# 780-00055_rev2_Pg4_SCH_NRES_Temp_Meas_8-.net
KiCad netlist of a schematic drawn in Altium Designer
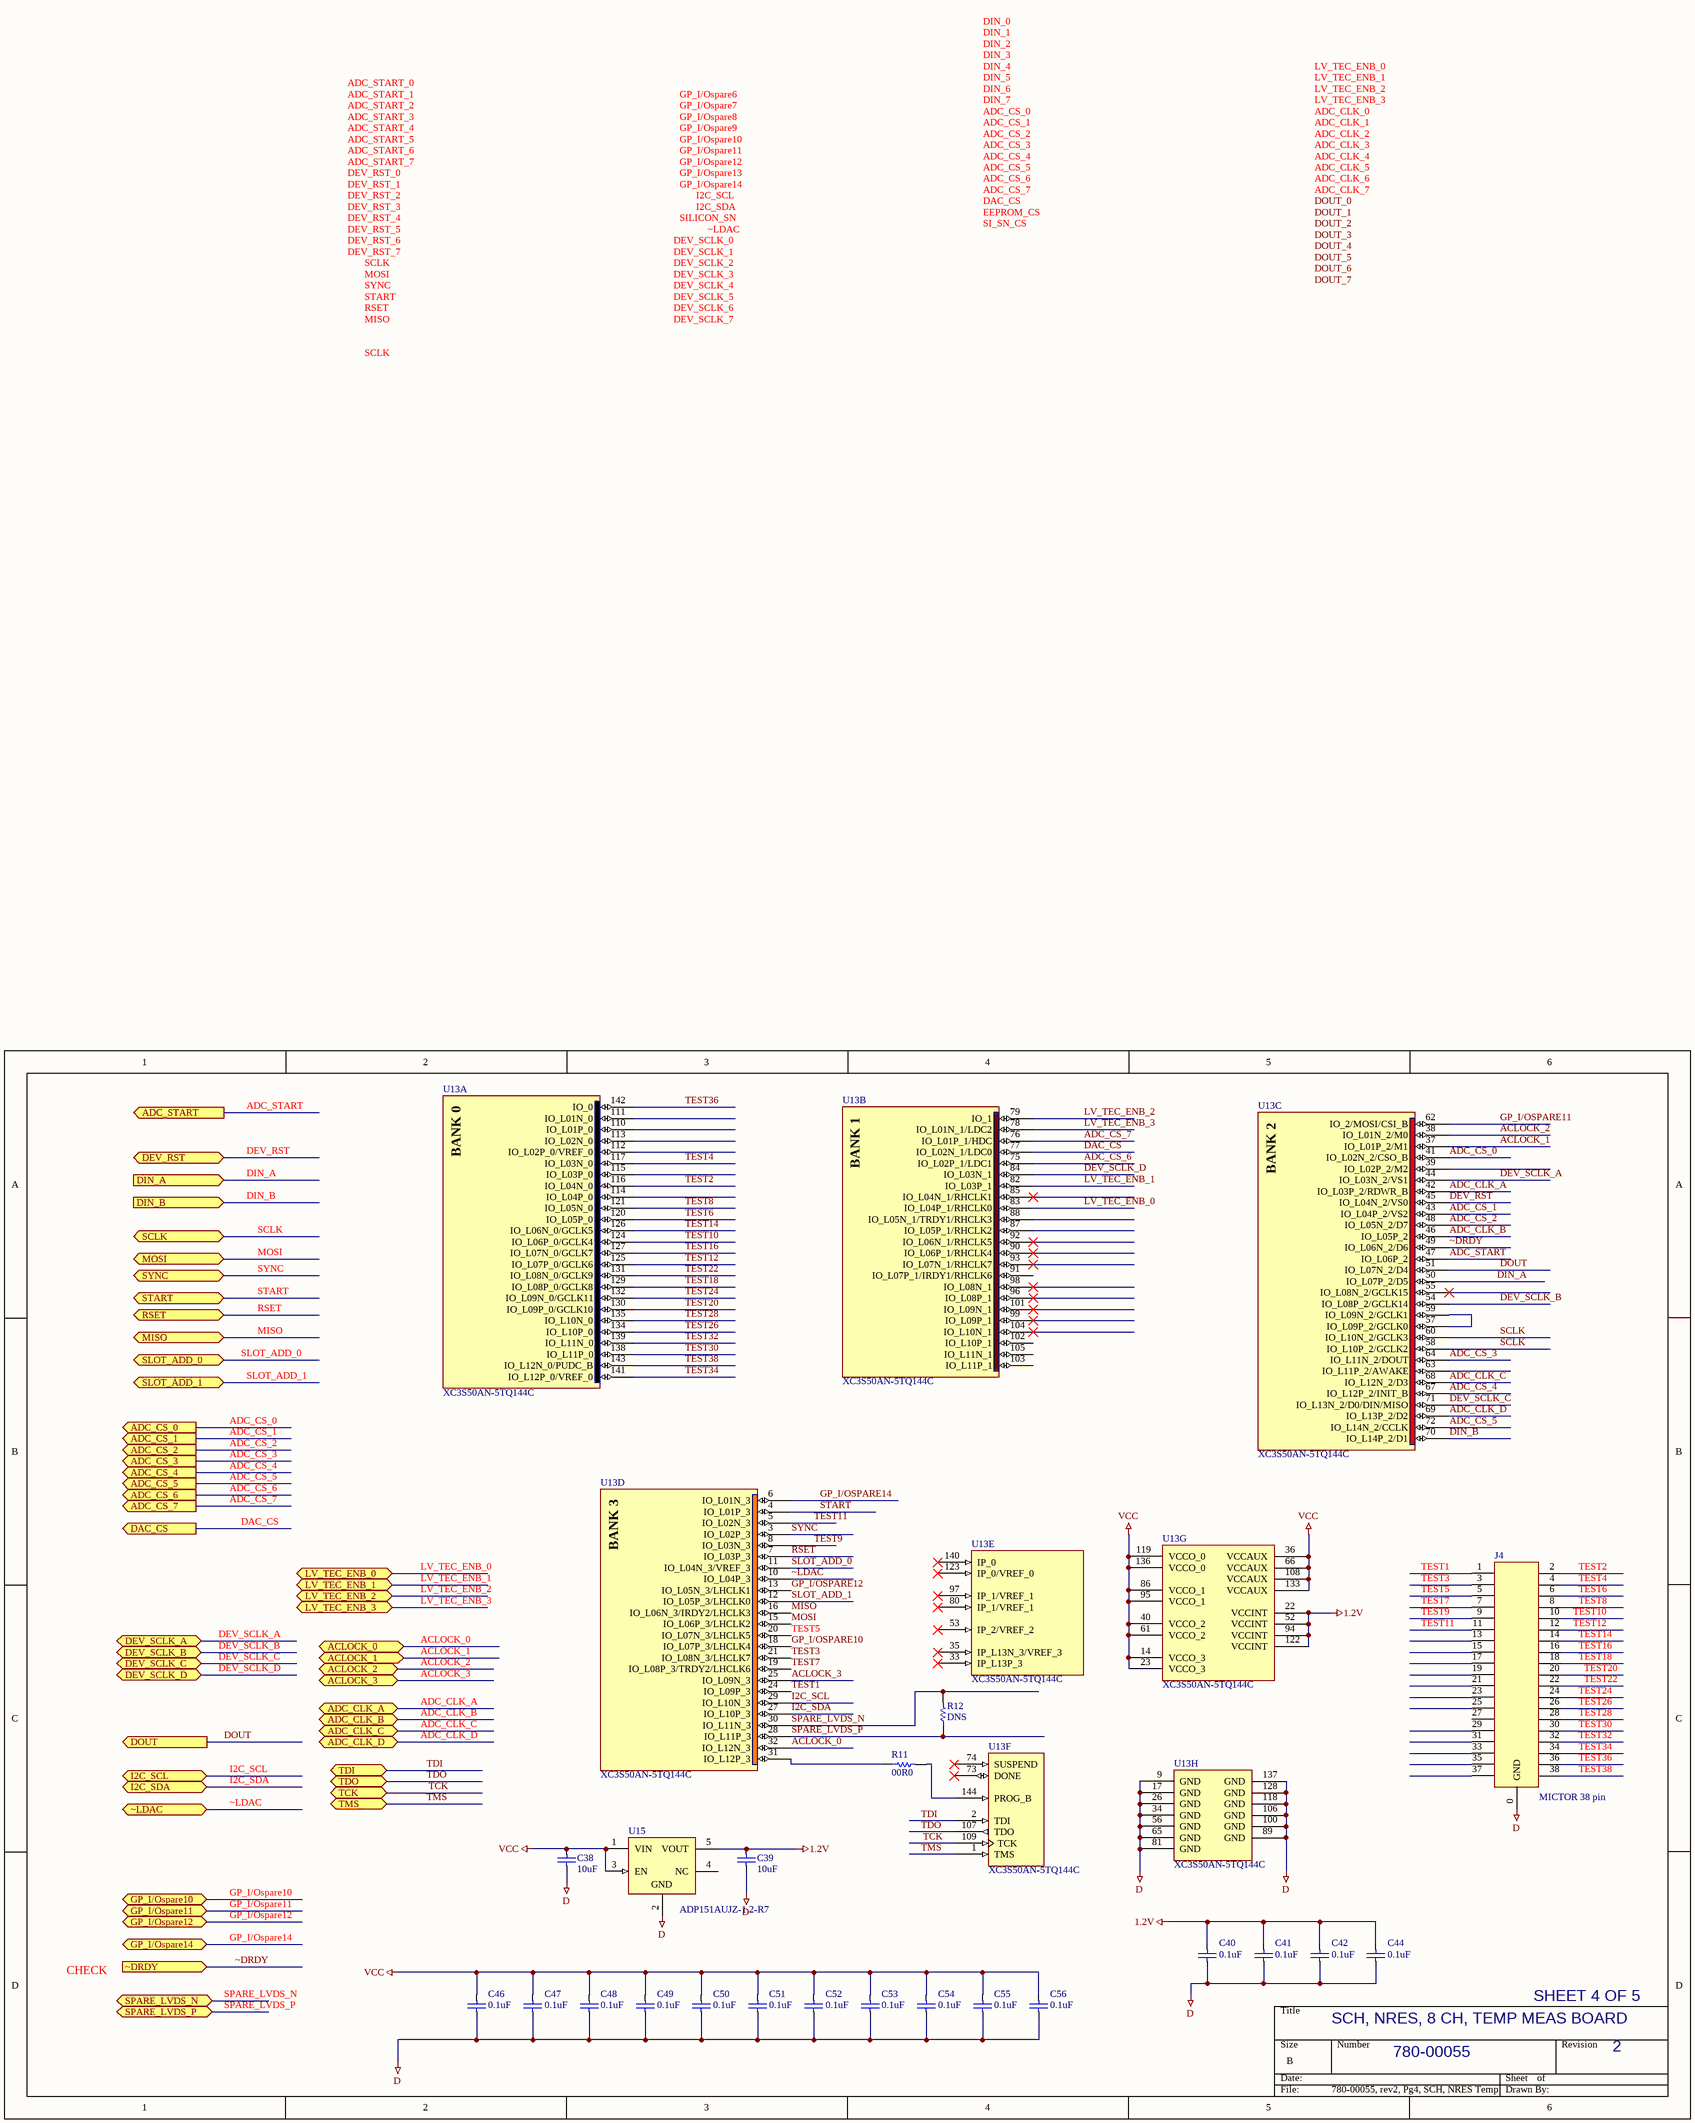
[diagram p0: 780-00055, rev2, Pg4, SCH, NRES Temp Meas, 8-Chan RTD .SchDoc]

(export (version "E")
  (design (tool "Eeschema 10.0.6"))
  (components
    (comp (ref "C38")
      (value "10uF")
      (footprint "Protel 99SE BANKS PCB:smd_0805")
      (description "Capacitor")
      (fields (field (name "Comment") "Cap SMD"))
      (libsource (lib "Richs Schematic Components") (part "Cap SMD"))
    )
    (comp (ref "C39")
      (value "10uF")
      (footprint "Protel 99SE BANKS PCB:smd_0805")
      (description "Capacitor")
      (fields (field (name "Comment") "Cap SMD"))
      (libsource (lib "Richs Schematic Components") (part "Cap SMD"))
    )
    (comp (ref "C40")
      (value "0.1uF")
      (footprint "SMD_0805")
      (description "Capacitor")
      (fields (field (name "Comment") "Cap SMD"))
      (libsource (lib "Richs Schematic Components") (part "Cap SMD"))
    )
    (comp (ref "C41")
      (value "0.1uF")
      (footprint "SMD_0805")
      (description "Capacitor")
      (fields (field (name "Comment") "Cap SMD"))
      (libsource (lib "Richs Schematic Components") (part "Cap SMD"))
    )
    (comp (ref "C42")
      (value "0.1uF")
      (footprint "SMD_0805")
      (description "Capacitor")
      (fields (field (name "Comment") "Cap SMD"))
      (libsource (lib "Richs Schematic Components") (part "Cap SMD"))
    )
    (comp (ref "C44")
      (value "0.1uF")
      (footprint "SMD_0805")
      (description "Capacitor")
      (fields (field (name "Comment") "Cap SMD"))
      (libsource (lib "Richs Schematic Components") (part "Cap SMD"))
    )
    (comp (ref "C46")
      (value "0.1uF")
      (footprint "SMD_0805")
      (description "Capacitor")
      (fields (field (name "Comment") "Cap SMD"))
      (libsource (lib "Richs Schematic Components") (part "Cap SMD"))
    )
    (comp (ref "C47")
      (value "0.1uF")
      (footprint "SMD_0805")
      (description "Capacitor")
      (fields (field (name "Comment") "Cap SMD"))
      (libsource (lib "Richs Schematic Components") (part "Cap SMD"))
    )
    (comp (ref "C48")
      (value "0.1uF")
      (footprint "SMD_0805")
      (description "Capacitor")
      (fields (field (name "Comment") "Cap SMD"))
      (libsource (lib "Richs Schematic Components") (part "Cap SMD"))
    )
    (comp (ref "C49")
      (value "0.1uF")
      (footprint "SMD_0805")
      (description "Capacitor")
      (fields (field (name "Comment") "Cap SMD"))
      (libsource (lib "Richs Schematic Components") (part "Cap SMD"))
    )
    (comp (ref "C50")
      (value "0.1uF")
      (footprint "SMD_0805")
      (description "Capacitor")
      (fields (field (name "Comment") "Cap SMD"))
      (libsource (lib "Richs Schematic Components") (part "Cap SMD"))
    )
    (comp (ref "C51")
      (value "0.1uF")
      (footprint "SMD_0805")
      (description "Capacitor")
      (fields (field (name "Comment") "Cap SMD"))
      (libsource (lib "Richs Schematic Components") (part "Cap SMD"))
    )
    (comp (ref "C52")
      (value "0.1uF")
      (footprint "SMD_0805")
      (description "Capacitor")
      (fields (field (name "Comment") "Cap SMD"))
      (libsource (lib "Richs Schematic Components") (part "Cap SMD"))
    )
    (comp (ref "C53")
      (value "0.1uF")
      (footprint "SMD_0805")
      (description "Capacitor")
      (fields (field (name "Comment") "Cap SMD"))
      (libsource (lib "Richs Schematic Components") (part "Cap SMD"))
    )
    (comp (ref "C54")
      (value "0.1uF")
      (footprint "SMD_0805")
      (description "Capacitor")
      (fields (field (name "Comment") "Cap SMD"))
      (libsource (lib "Richs Schematic Components") (part "Cap SMD"))
    )
    (comp (ref "C55")
      (value "0.1uF")
      (footprint "SMD_0805")
      (description "Capacitor")
      (fields (field (name "Comment") "Cap SMD"))
      (libsource (lib "Richs Schematic Components") (part "Cap SMD"))
    )
    (comp (ref "C56")
      (value "0.1uF")
      (footprint "SMD_0805")
      (description "Capacitor")
      (fields (field (name "Comment") "Cap SMD"))
      (libsource (lib "Richs Schematic Components") (part "Cap SMD"))
    )
    (comp (ref "J4")
      (value "MICTOR 38 pin")
      (footprint "MICTOR 38 pin connector")
      (description "38 pin MICTOR Adapter")
      (fields (field (name "MANUFACTURER") "TE Connectivity"))
      (libsource (lib "Richs Schematic Components") (part "MICTOR Adapter"))
    )
    (comp (ref "R11")
      (value "00R0")
      (footprint "SMD_0805")
      (description "Resistor 0805")
      (fields (field (name "MANUFACTURER") "Vishay/Dale") (field (name "Comment") "Res 0805"))
      (libsource (lib "Richs Schematic Components") (part "Res SMD"))
    )
    (comp (ref "R12")
      (value "DNS")
      (footprint "SMD_0805")
      (description "Resistor 0805")
      (fields (field (name "MANUFACTURER") "Vishay/Dale") (field (name "Comment") "Res 0805"))
      (libsource (lib "Richs Schematic Components") (part "Res SMD"))
    )
    (comp (ref "U13")
      (value "XC3S50AN-5TQ144C")
      (footprint "TQ144_N")
      (description "Spartan-3AN Non-Volatile FPGA, 108 User I/Os, 144-Pin TQFP, High Performance, Commercial Grade")
      (fields (field (name "PUBLISHER") "Altium Limited"))
      (libsource (lib "Xilinx Spartan-3AN") (part "XC3S50AN-5TQ144C"))
    )
    (comp (ref "U15")
      (value "ADP151AUJZ-1.2-R7")
      (footprint "ADI-UJ-5_N")
      (fields (field (name "MANUFACTURER") "Analog Devices"))
      (libsource (lib "Altium Content Vault") (part "ADI-ADP1XX-UJ-5"))
    )
  )
  (nets
    (net (code "1") (name "/ACLOCK_0") (class "Default")
      (node (ref "U13") (pin "32") (pinfunction "IO_L12N_3_32") (pintype "bidirectional"))
    )
    (net (code "2") (name "/ACLOCK_1") (class "Default")
      (node (ref "U13") (pin "37") (pinfunction "IO_L01P_2/M1_37") (pintype "bidirectional"))
    )
    (net (code "3") (name "/ACLOCK_2") (class "Default")
      (node (ref "U13") (pin "38") (pinfunction "IO_L01N_2/M0_38") (pintype "bidirectional"))
    )
    (net (code "4") (name "/ACLOCK_3") (class "Default")
      (node (ref "U13") (pin "25") (pinfunction "IO_L09N_3_25") (pintype "bidirectional"))
    )
    (net (code "13") (name "/ADC_CLK_A") (class "Default")
      (node (ref "U13") (pin "42") (pinfunction "IO_L03P_2/RDWR_B_42") (pintype "bidirectional"))
    )
    (net (code "14") (name "/ADC_CLK_B") (class "Default")
      (node (ref "U13") (pin "46") (pinfunction "IO_L05P_2_46") (pintype "bidirectional"))
    )
    (net (code "15") (name "/ADC_CLK_C") (class "Default")
      (node (ref "U13") (pin "68") (pinfunction "IO_L12N_2/D3_68") (pintype "bidirectional"))
    )
    (net (code "16") (name "/ADC_CLK_D") (class "Default")
      (node (ref "U13") (pin "69") (pinfunction "IO_L13P_2/D2_69") (pintype "bidirectional"))
    )
    (net (code "17") (name "/ADC_CS_0") (class "Default")
      (node (ref "U13") (pin "41") (pinfunction "IO_L02N_2/CSO_B_41") (pintype "bidirectional"))
    )
    (net (code "18") (name "/ADC_CS_1") (class "Default")
      (node (ref "U13") (pin "43") (pinfunction "IO_L04P_2/VS2_43") (pintype "bidirectional"))
    )
    (net (code "19") (name "/ADC_CS_2") (class "Default")
      (node (ref "U13") (pin "48") (pinfunction "IO_L05N_2/D7_48") (pintype "bidirectional"))
    )
    (net (code "20") (name "/ADC_CS_3") (class "Default")
      (node (ref "U13") (pin "64") (pinfunction "IO_L11N_2/DOUT_64") (pintype "bidirectional"))
    )
    (net (code "21") (name "/ADC_CS_4") (class "Default")
      (node (ref "U13") (pin "67") (pinfunction "IO_L12P_2/INIT_B_67") (pintype "bidirectional"))
    )
    (net (code "22") (name "/ADC_CS_5") (class "Default")
      (node (ref "U13") (pin "72") (pinfunction "IO_L14N_2/CCLK_72") (pintype "bidirectional"))
    )
    (net (code "23") (name "/ADC_CS_6") (class "Default")
      (node (ref "U13") (pin "75") (pinfunction "IO_L02P_1/LDC1_75") (pintype "bidirectional"))
    )
    (net (code "24") (name "/ADC_CS_7") (class "Default")
      (node (ref "U13") (pin "76") (pinfunction "IO_L01P_1/HDC_76") (pintype "bidirectional"))
    )
    (net (code "25") (name "/ADC_START") (class "Default")
      (node (ref "U13") (pin "47") (pinfunction "IO_L06P_2_47") (pintype "bidirectional"))
    )
    (net (code "34") (name "/DAC_CS") (class "Default")
      (node (ref "U13") (pin "77") (pinfunction "IO_L02N_1/LDC0_77") (pintype "bidirectional"))
    )
    (net (code "35") (name "/DEV_RST") (class "Default")
      (node (ref "U13") (pin "45") (pinfunction "IO_L04N_2/VS0_45") (pintype "bidirectional"))
    )
    (net (code "52") (name "/DEV_SCLK_A") (class "Default")
      (node (ref "U13") (pin "44") (pinfunction "IO_L03N_2/VS1_44") (pintype "bidirectional"))
    )
    (net (code "53") (name "/DEV_SCLK_B") (class "Default")
      (node (ref "U13") (pin "54") (pinfunction "IO_L08P_2/GCLK14_54") (pintype "bidirectional"))
    )
    (net (code "54") (name "/DEV_SCLK_C") (class "Default")
      (node (ref "U13") (pin "71") (pinfunction "IO_L13N_2/D0/DIN/MISO_71") (pintype "bidirectional"))
    )
    (net (code "55") (name "/DEV_SCLK_D") (class "Default")
      (node (ref "U13") (pin "84") (pinfunction "IO_L03N_1_84") (pintype "bidirectional"))
    )
    (net (code "64") (name "/DIN_A") (class "Default")
      (node (ref "U13") (pin "50") (pinfunction "IO_L07P_2/D5_50") (pintype "bidirectional"))
    )
    (net (code "65") (name "/DIN_B") (class "Default")
      (node (ref "U13") (pin "70") (pinfunction "IO_L14P_2/D1_70") (pintype "bidirectional"))
    )
    (net (code "66") (name "/DOUT") (class "Default")
      (node (ref "U13") (pin "51") (pinfunction "IO_L07N_2/D4_51") (pintype "bidirectional"))
    )
    (net (code "76") (name "/GP_I{slash}OSPARE10") (class "Default")
      (node (ref "U13") (pin "18") (pinfunction "IO_L07P_3/LHCLK4_18") (pintype "bidirectional"))
    )
    (net (code "77") (name "/GP_I{slash}OSPARE11") (class "Default")
      (node (ref "U13") (pin "62") (pinfunction "IO_2/MOSI/CSI_B_62") (pintype "bidirectional"))
    )
    (net (code "78") (name "/GP_I{slash}OSPARE12") (class "Default")
      (node (ref "U13") (pin "13") (pinfunction "IO_L05N_3/LHCLK1_13") (pintype "bidirectional"))
    )
    (net (code "79") (name "/GP_I{slash}OSPARE14") (class "Default")
      (node (ref "U13") (pin "6") (pinfunction "IO_L01N_3_6") (pintype "bidirectional"))
    )
    (net (code "89") (name "/I2C_SCL") (class "Default")
      (node (ref "U13") (pin "29") (pinfunction "IO_L10N_3_29") (pintype "bidirectional"))
    )
    (net (code "90") (name "/I2C_SDA") (class "Default")
      (node (ref "U13") (pin "27") (pinfunction "IO_L10P_3_27") (pintype "bidirectional"))
    )
    (net (code "91") (name "/LV_TEC_ENB_0") (class "Default")
      (node (ref "U13") (pin "83") (pinfunction "IO_L04P_1/RHCLK0_83") (pintype "bidirectional"))
    )
    (net (code "92") (name "/LV_TEC_ENB_1") (class "Default")
      (node (ref "U13") (pin "82") (pinfunction "IO_L03P_1_82") (pintype "bidirectional"))
    )
    (net (code "93") (name "/LV_TEC_ENB_2") (class "Default")
      (node (ref "U13") (pin "79") (pinfunction "IO_1_79") (pintype "bidirectional"))
    )
    (net (code "94") (name "/LV_TEC_ENB_3") (class "Default")
      (node (ref "U13") (pin "78") (pinfunction "IO_L01N_1/LDC2_78") (pintype "bidirectional"))
    )
    (net (code "95") (name "/MISO") (class "Default")
      (node (ref "U13") (pin "16") (pinfunction "IO_L06N_3/IRDY2/LHCLK3_16") (pintype "bidirectional"))
    )
    (net (code "96") (name "/MOSI") (class "Default")
      (node (ref "U13") (pin "15") (pinfunction "IO_L06P_3/LHCLK2_15") (pintype "bidirectional"))
    )
    (net (code "97") (name "/RSET") (class "Default")
      (node (ref "U13") (pin "7") (pinfunction "IO_L03P_3_7") (pintype "bidirectional"))
    )
    (net (code "98") (name "/SCLK") (class "Default")
      (node (ref "U13") (pin "58") (pinfunction "IO_L10P_2/GCLK2_58") (pintype "bidirectional"))
      (node (ref "U13") (pin "60") (pinfunction "IO_L10N_2/GCLK3_60") (pintype "bidirectional"))
    )
    (net (code "101") (name "/SLOT_ADD_0") (class "Default")
      (node (ref "U13") (pin "11") (pinfunction "IO_L04N_3/VREF_3_11") (pintype "bidirectional"))
    )
    (net (code "102") (name "/SLOT_ADD_1") (class "Default")
      (node (ref "U13") (pin "12") (pinfunction "IO_L05P_3/LHCLK0_12") (pintype "bidirectional"))
    )
    (net (code "103") (name "/SPARE_LVDS_N") (class "Default")
      (node (ref "R12") (pin "2") (pinfunction "2_2") (pintype "passive"))
      (node (ref "U13") (pin "30") (pinfunction "IO_L11N_3_30") (pintype "bidirectional"))
    )
    (net (code "104") (name "/SPARE_LVDS_P") (class "Default")
      (node (ref "R12") (pin "1") (pinfunction "1_1") (pintype "passive"))
      (node (ref "U13") (pin "28") (pinfunction "IO_L11P_3_28") (pintype "bidirectional"))
    )
    (net (code "105") (name "/START") (class "Default")
      (node (ref "U13") (pin "4") (pinfunction "IO_L01P_3_4") (pintype "bidirectional"))
    )
    (net (code "106") (name "/SYNC") (class "Default")
      (node (ref "U13") (pin "3") (pinfunction "IO_L02P_3_3") (pintype "bidirectional"))
    )
    (net (code "107") (name "/TCK") (class "Default")
      (node (ref "U13") (pin "109") (pinfunction "TCK_109") (pintype "input"))
    )
    (net (code "108") (name "/TDI") (class "Default")
      (node (ref "U13") (pin "2") (pinfunction "TDI_2") (pintype "input"))
    )
    (net (code "109") (name "/TDO") (class "Default")
      (node (ref "U13") (pin "107") (pinfunction "TDO_107") (pintype "output"))
    )
    (net (code "110") (name "/TEST1") (class "Default")
      (node (ref "J4") (pin "1") (pinfunction "display_1") (pintype "passive"))
      (node (ref "U13") (pin "24") (pinfunction "IO_L09P_3_24") (pintype "bidirectional"))
    )
    (net (code "111") (name "/TEST2") (class "Default")
      (node (ref "J4") (pin "2") (pinfunction "conn_2") (pintype "passive"))
      (node (ref "U13") (pin "116") (pinfunction "IO_L04N_0_116") (pintype "bidirectional"))
    )
    (net (code "112") (name "/TEST3") (class "Default")
      (node (ref "J4") (pin "3") (pinfunction "conn_3") (pintype "passive"))
      (node (ref "U13") (pin "21") (pinfunction "IO_L08N_3/LHCLK7_21") (pintype "bidirectional"))
    )
    (net (code "113") (name "/TEST4") (class "Default")
      (node (ref "J4") (pin "4") (pinfunction "conn_4") (pintype "passive"))
      (node (ref "U13") (pin "117") (pinfunction "IO_L03N_0_117") (pintype "bidirectional"))
    )
    (net (code "114") (name "/TEST5") (class "Default")
      (node (ref "J4") (pin "5") (pinfunction "conn_5") (pintype "passive"))
      (node (ref "U13") (pin "20") (pinfunction "IO_L07N_3/LHCLK5_20") (pintype "bidirectional"))
    )
    (net (code "115") (name "/TEST6") (class "Default")
      (node (ref "J4") (pin "6") (pinfunction "conn_6") (pintype "passive"))
      (node (ref "U13") (pin "120") (pinfunction "IO_L05P_0_120") (pintype "bidirectional"))
    )
    (net (code "116") (name "/TEST7") (class "Default")
      (node (ref "J4") (pin "7") (pinfunction "conn_7") (pintype "passive"))
      (node (ref "U13") (pin "19") (pinfunction "IO_L08P_3/TRDY2/LHCLK6_19") (pintype "bidirectional"))
    )
    (net (code "117") (name "/TEST8") (class "Default")
      (node (ref "J4") (pin "8") (pinfunction "conn_8") (pintype "passive"))
      (node (ref "U13") (pin "121") (pinfunction "IO_L05N_0_121") (pintype "bidirectional"))
    )
    (net (code "118") (name "/TEST9") (class "Default")
      (node (ref "J4") (pin "9") (pinfunction "conn_9") (pintype "passive"))
      (node (ref "U13") (pin "8") (pinfunction "IO_L03N_3_8") (pintype "bidirectional"))
    )
    (net (code "119") (name "/TEST10") (class "Default")
      (node (ref "J4") (pin "10") (pinfunction "conn_10") (pintype "passive"))
      (node (ref "U13") (pin "124") (pinfunction "IO_L06P_0/GCLK4_124") (pintype "bidirectional"))
    )
    (net (code "120") (name "/TEST11") (class "Default")
      (node (ref "J4") (pin "11") (pinfunction "conn_11") (pintype "passive"))
      (node (ref "U13") (pin "5") (pinfunction "IO_L02N_3_5") (pintype "bidirectional"))
    )
    (net (code "121") (name "/TEST12") (class "Default")
      (node (ref "J4") (pin "12") (pinfunction "conn_12") (pintype "passive"))
      (node (ref "U13") (pin "125") (pinfunction "IO_L07P_0/GCLK6_125") (pintype "bidirectional"))
    )
    (net (code "122") (name "/TEST14") (class "Default")
      (node (ref "J4") (pin "14") (pinfunction "conn_14") (pintype "passive"))
      (node (ref "U13") (pin "126") (pinfunction "IO_L06N_0/GCLK5_126") (pintype "bidirectional"))
    )
    (net (code "123") (name "/TEST16") (class "Default")
      (node (ref "J4") (pin "16") (pinfunction "conn_16") (pintype "passive"))
      (node (ref "U13") (pin "127") (pinfunction "IO_L07N_0/GCLK7_127") (pintype "bidirectional"))
    )
    (net (code "124") (name "/TEST18") (class "Default")
      (node (ref "J4") (pin "18") (pinfunction "conn_18") (pintype "passive"))
      (node (ref "U13") (pin "129") (pinfunction "IO_L08P_0/GCLK8_129") (pintype "bidirectional"))
    )
    (net (code "125") (name "/TEST20") (class "Default")
      (node (ref "J4") (pin "20") (pinfunction "conn_20") (pintype "passive"))
      (node (ref "U13") (pin "130") (pinfunction "IO_L09P_0/GCLK10_130") (pintype "bidirectional"))
    )
    (net (code "126") (name "/TEST22") (class "Default")
      (node (ref "J4") (pin "22") (pinfunction "conn_22") (pintype "passive"))
      (node (ref "U13") (pin "131") (pinfunction "IO_L08N_0/GCLK9_131") (pintype "bidirectional"))
    )
    (net (code "127") (name "/TEST24") (class "Default")
      (node (ref "J4") (pin "24") (pinfunction "conn_24") (pintype "passive"))
      (node (ref "U13") (pin "132") (pinfunction "IO_L09N_0/GCLK11_132") (pintype "bidirectional"))
    )
    (net (code "128") (name "/TEST26") (class "Default")
      (node (ref "J4") (pin "26") (pinfunction "conn_26") (pintype "passive"))
      (node (ref "U13") (pin "134") (pinfunction "IO_L10P_0_134") (pintype "bidirectional"))
    )
    (net (code "129") (name "/TEST28") (class "Default")
      (node (ref "J4") (pin "28") (pinfunction "conn_28") (pintype "passive"))
      (node (ref "U13") (pin "135") (pinfunction "IO_L10N_0_135") (pintype "bidirectional"))
    )
    (net (code "130") (name "/TEST30") (class "Default")
      (node (ref "J4") (pin "30") (pinfunction "conn_30") (pintype "passive"))
      (node (ref "U13") (pin "138") (pinfunction "IO_L11P_0_138") (pintype "bidirectional"))
    )
    (net (code "131") (name "/TEST32") (class "Default")
      (node (ref "J4") (pin "32") (pinfunction "conn_32") (pintype "passive"))
      (node (ref "U13") (pin "139") (pinfunction "IO_L11N_0_139") (pintype "bidirectional"))
    )
    (net (code "132") (name "/TEST34") (class "Default")
      (node (ref "J4") (pin "34") (pinfunction "conn_34") (pintype "passive"))
      (node (ref "U13") (pin "141") (pinfunction "IO_L12P_0/VREF_0_141") (pintype "bidirectional"))
    )
    (net (code "133") (name "/TEST36") (class "Default")
      (node (ref "J4") (pin "36") (pinfunction "conn_36") (pintype "passive"))
      (node (ref "U13") (pin "142") (pinfunction "IO_0_142") (pintype "bidirectional"))
    )
    (net (code "134") (name "/TEST38") (class "Default")
      (node (ref "J4") (pin "38") (pinfunction "conn_38") (pintype "passive"))
      (node (ref "U13") (pin "143") (pinfunction "IO_L12N_0/PUDC_B_143") (pintype "bidirectional"))
    )
    (net (code "135") (name "/TMS") (class "Default")
      (node (ref "U13") (pin "1") (pinfunction "TMS_1") (pintype "input"))
    )
    (net (code "136") (name "/~DRDY") (class "Default")
      (node (ref "U13") (pin "49") (pinfunction "IO_L06N_2/D6_49") (pintype "bidirectional"))
    )
    (net (code "137") (name "/~LDAC") (class "Default")
      (node (ref "U13") (pin "10") (pinfunction "IO_L04P_3_10") (pintype "bidirectional"))
    )
    (net (code "138") (name "1.2V") (class "Default")
      (node (ref "C39") (pin "2") (pinfunction "2_2") (pintype "passive"))
      (node (ref "C40") (pin "2") (pinfunction "2_2") (pintype "passive"))
      (node (ref "C41") (pin "2") (pinfunction "2_2") (pintype "passive"))
      (node (ref "C42") (pin "2") (pinfunction "2_2") (pintype "passive"))
      (node (ref "C44") (pin "2") (pinfunction "2_2") (pintype "passive"))
      (node (ref "U13") (pin "122") (pinfunction "VCCINT_122") (pintype "power_in"))
      (node (ref "U13") (pin "22") (pinfunction "VCCINT_22") (pintype "power_in"))
      (node (ref "U13") (pin "52") (pinfunction "VCCINT_52") (pintype "power_in"))
      (node (ref "U13") (pin "94") (pinfunction "VCCINT_94") (pintype "power_in"))
      (node (ref "U15") (pin "5") (pinfunction "VOUT_5") (pintype "power_in"))
    )
    (net (code "139") (name "D") (class "Default")
      (node (ref "C38") (pin "1") (pinfunction "1_1") (pintype "passive"))
      (node (ref "C39") (pin "1") (pinfunction "1_1") (pintype "passive"))
      (node (ref "C40") (pin "1") (pinfunction "1_1") (pintype "passive"))
      (node (ref "C41") (pin "1") (pinfunction "1_1") (pintype "passive"))
      (node (ref "C42") (pin "1") (pinfunction "1_1") (pintype "passive"))
      (node (ref "C44") (pin "1") (pinfunction "1_1") (pintype "passive"))
      (node (ref "C46") (pin "1") (pinfunction "1_1") (pintype "passive"))
      (node (ref "C47") (pin "1") (pinfunction "1_1") (pintype "passive"))
      (node (ref "C48") (pin "1") (pinfunction "1_1") (pintype "passive"))
      (node (ref "C49") (pin "1") (pinfunction "1_1") (pintype "passive"))
      (node (ref "C50") (pin "1") (pinfunction "1_1") (pintype "passive"))
      (node (ref "C51") (pin "1") (pinfunction "1_1") (pintype "passive"))
      (node (ref "C52") (pin "1") (pinfunction "1_1") (pintype "passive"))
      (node (ref "C53") (pin "1") (pinfunction "1_1") (pintype "passive"))
      (node (ref "C54") (pin "1") (pinfunction "1_1") (pintype "passive"))
      (node (ref "C55") (pin "1") (pinfunction "1_1") (pintype "passive"))
      (node (ref "C56") (pin "1") (pinfunction "1_1") (pintype "passive"))
      (node (ref "J4") (pin "0") (pinfunction "GND_0") (pintype "passive"))
      (node (ref "U13") (pin "100") (pinfunction "GND_100") (pintype "power_in"))
      (node (ref "U13") (pin "106") (pinfunction "GND_106") (pintype "power_in"))
      (node (ref "U13") (pin "118") (pinfunction "GND_118") (pintype "power_in"))
      (node (ref "U13") (pin "128") (pinfunction "GND_128") (pintype "power_in"))
      (node (ref "U13") (pin "137") (pinfunction "GND_137") (pintype "power_in"))
      (node (ref "U13") (pin "17") (pinfunction "GND_17") (pintype "power_in"))
      (node (ref "U13") (pin "26") (pinfunction "GND_26") (pintype "power_in"))
      (node (ref "U13") (pin "34") (pinfunction "GND_34") (pintype "power_in"))
      (node (ref "U13") (pin "56") (pinfunction "GND_56") (pintype "power_in"))
      (node (ref "U13") (pin "65") (pinfunction "GND_65") (pintype "power_in"))
      (node (ref "U13") (pin "81") (pinfunction "GND_81") (pintype "power_in"))
      (node (ref "U13") (pin "89") (pinfunction "GND_89") (pintype "power_in"))
      (node (ref "U13") (pin "9") (pinfunction "GND_9") (pintype "power_in"))
      (node (ref "U15") (pin "2") (pinfunction "GND_2") (pintype "power_in"))
    )
    (net (code "140") (name "Net-(U13C-IO_L09N_2{slash}GCLK1)") (class "Default")
      (node (ref "U13") (pin "57") (pinfunction "IO_L09P_2/GCLK0_57") (pintype "bidirectional"))
      (node (ref "U13") (pin "59") (pinfunction "IO_L09N_2/GCLK1_59") (pintype "bidirectional"))
    )
    (net (code "141") (name "Net-(U13D-IO_L12P_3)") (class "Default")
      (node (ref "R11") (pin "1") (pinfunction "1_1") (pintype "passive"))
      (node (ref "U13") (pin "31") (pinfunction "IO_L12P_3_31") (pintype "bidirectional"))
    )
    (net (code "142") (name "Net-(U13F-PROG_B)") (class "Default")
      (node (ref "R11") (pin "2") (pinfunction "2_2") (pintype "passive"))
      (node (ref "U13") (pin "144") (pinfunction "PROG_B_144") (pintype "input"))
    )
    (net (code "143") (name "VCC") (class "Default")
      (node (ref "C38") (pin "2") (pinfunction "2_2") (pintype "passive"))
      (node (ref "C46") (pin "2") (pinfunction "2_2") (pintype "passive"))
      (node (ref "C47") (pin "2") (pinfunction "2_2") (pintype "passive"))
      (node (ref "C48") (pin "2") (pinfunction "2_2") (pintype "passive"))
      (node (ref "C49") (pin "2") (pinfunction "2_2") (pintype "passive"))
      (node (ref "C50") (pin "2") (pinfunction "2_2") (pintype "passive"))
      (node (ref "C51") (pin "2") (pinfunction "2_2") (pintype "passive"))
      (node (ref "C52") (pin "2") (pinfunction "2_2") (pintype "passive"))
      (node (ref "C53") (pin "2") (pinfunction "2_2") (pintype "passive"))
      (node (ref "C54") (pin "2") (pinfunction "2_2") (pintype "passive"))
      (node (ref "C55") (pin "2") (pinfunction "2_2") (pintype "passive"))
      (node (ref "C56") (pin "2") (pinfunction "2_2") (pintype "passive"))
      (node (ref "U13") (pin "108") (pinfunction "VCCAUX_108") (pintype "power_in"))
      (node (ref "U13") (pin "119") (pinfunction "VCCO_0_119") (pintype "power_in"))
      (node (ref "U13") (pin "133") (pinfunction "VCCAUX_133") (pintype "power_in"))
      (node (ref "U13") (pin "136") (pinfunction "VCCO_0_136") (pintype "power_in"))
      (node (ref "U13") (pin "14") (pinfunction "VCCO_3_14") (pintype "power_in"))
      (node (ref "U13") (pin "23") (pinfunction "VCCO_3_23") (pintype "power_in"))
      (node (ref "U13") (pin "36") (pinfunction "VCCAUX_36") (pintype "power_in"))
      (node (ref "U13") (pin "40") (pinfunction "VCCO_2_40") (pintype "power_in"))
      (node (ref "U13") (pin "61") (pinfunction "VCCO_2_61") (pintype "power_in"))
      (node (ref "U13") (pin "66") (pinfunction "VCCAUX_66") (pintype "power_in"))
      (node (ref "U13") (pin "86") (pinfunction "VCCO_1_86") (pintype "power_in"))
      (node (ref "U13") (pin "95") (pinfunction "VCCO_1_95") (pintype "power_in"))
      (node (ref "U15") (pin "1") (pinfunction "VIN_1") (pintype "power_in"))
      (node (ref "U15") (pin "3") (pinfunction "EN_3") (pintype "input"))
    )
    (net (code "144") (name "unconnected-(J4-conn-Pad13)") (class "Default")
      (node (ref "J4") (pin "13") (pinfunction "conn_13") (pintype "passive"))
    )
    (net (code "145") (name "unconnected-(J4-conn-Pad15)") (class "Default")
      (node (ref "J4") (pin "15") (pinfunction "conn_15") (pintype "passive"))
    )
    (net (code "146") (name "unconnected-(J4-conn-Pad17)") (class "Default")
      (node (ref "J4") (pin "17") (pinfunction "conn_17") (pintype "passive"))
    )
    (net (code "147") (name "unconnected-(J4-conn-Pad19)") (class "Default")
      (node (ref "J4") (pin "19") (pinfunction "conn_19") (pintype "passive"))
    )
    (net (code "148") (name "unconnected-(J4-conn-Pad21)") (class "Default")
      (node (ref "J4") (pin "21") (pinfunction "conn_21") (pintype "passive"))
    )
    (net (code "149") (name "unconnected-(J4-conn-Pad23)") (class "Default")
      (node (ref "J4") (pin "23") (pinfunction "conn_23") (pintype "passive"))
    )
    (net (code "150") (name "unconnected-(J4-conn-Pad25)") (class "Default")
      (node (ref "J4") (pin "25") (pinfunction "conn_25") (pintype "passive"))
    )
    (net (code "151") (name "unconnected-(J4-conn-Pad27)") (class "Default")
      (node (ref "J4") (pin "27") (pinfunction "conn_27") (pintype "passive"))
    )
    (net (code "152") (name "unconnected-(J4-conn-Pad29)") (class "Default")
      (node (ref "J4") (pin "29") (pinfunction "conn_29") (pintype "passive"))
    )
    (net (code "153") (name "unconnected-(J4-conn-Pad31)") (class "Default")
      (node (ref "J4") (pin "31") (pinfunction "conn_31") (pintype "passive"))
    )
    (net (code "154") (name "unconnected-(J4-conn-Pad33)") (class "Default")
      (node (ref "J4") (pin "33") (pinfunction "conn_33") (pintype "passive"))
    )
    (net (code "155") (name "unconnected-(J4-conn-Pad35)") (class "Default")
      (node (ref "J4") (pin "35") (pinfunction "conn_35") (pintype "passive"))
    )
    (net (code "156") (name "unconnected-(J4-conn-Pad37)") (class "Default")
      (node (ref "J4") (pin "37") (pinfunction "conn_37") (pintype "passive"))
    )
    (net (code "157") (name "unconnected-(U13A-IO_L01N_0-Pad111)") (class "Default")
      (node (ref "U13") (pin "111") (pinfunction "IO_L01N_0_111") (pintype "bidirectional"))
    )
    (net (code "158") (name "unconnected-(U13A-IO_L01P_0-Pad110)") (class "Default")
      (node (ref "U13") (pin "110") (pinfunction "IO_L01P_0_110") (pintype "bidirectional"))
    )
    (net (code "159") (name "unconnected-(U13A-IO_L02N_0-Pad113)") (class "Default")
      (node (ref "U13") (pin "113") (pinfunction "IO_L02N_0_113") (pintype "bidirectional"))
    )
    (net (code "160") (name "unconnected-(U13A-IO_L02P_0{slash}VREF_0-Pad112)") (class "Default")
      (node (ref "U13") (pin "112") (pinfunction "IO_L02P_0/VREF_0_112") (pintype "bidirectional"))
    )
    (net (code "161") (name "unconnected-(U13A-IO_L03P_0-Pad115)") (class "Default")
      (node (ref "U13") (pin "115") (pinfunction "IO_L03P_0_115") (pintype "bidirectional"))
    )
    (net (code "162") (name "unconnected-(U13A-IO_L04P_0-Pad114)") (class "Default")
      (node (ref "U13") (pin "114") (pinfunction "IO_L04P_0_114") (pintype "bidirectional"))
    )
    (net (code "163") (name "unconnected-(U13B-IO_L04N_1{slash}RHCLK1-Pad85)") (class "Default")
      (node (ref "U13") (pin "85") (pinfunction "IO_L04N_1/RHCLK1_85") (pintype "bidirectional+no_connect"))
    )
    (net (code "164") (name "unconnected-(U13B-IO_L05N_1{slash}TRDY1{slash}RHCLK3-Pad88)") (class "Default")
      (node (ref "U13") (pin "88") (pinfunction "IO_L05N_1/TRDY1/RHCLK3_88") (pintype "bidirectional"))
    )
    (net (code "165") (name "unconnected-(U13B-IO_L05P_1{slash}RHCLK2-Pad87)") (class "Default")
      (node (ref "U13") (pin "87") (pinfunction "IO_L05P_1/RHCLK2_87") (pintype "bidirectional"))
    )
    (net (code "166") (name "unconnected-(U13B-IO_L06N_1{slash}RHCLK5-Pad92)") (class "Default")
      (node (ref "U13") (pin "92") (pinfunction "IO_L06N_1/RHCLK5_92") (pintype "bidirectional+no_connect"))
    )
    (net (code "167") (name "unconnected-(U13B-IO_L06P_1{slash}RHCLK4-Pad90)") (class "Default")
      (node (ref "U13") (pin "90") (pinfunction "IO_L06P_1/RHCLK4_90") (pintype "bidirectional+no_connect"))
    )
    (net (code "168") (name "unconnected-(U13B-IO_L07N_1{slash}RHCLK7-Pad93)") (class "Default")
      (node (ref "U13") (pin "93") (pinfunction "IO_L07N_1/RHCLK7_93") (pintype "bidirectional+no_connect"))
    )
    (net (code "169") (name "unconnected-(U13B-IO_L07P_1{slash}IRDY1{slash}RHCLK6-Pad91)") (class "Default")
      (node (ref "U13") (pin "91") (pinfunction "IO_L07P_1/IRDY1/RHCLK6_91") (pintype "bidirectional"))
    )
    (net (code "170") (name "unconnected-(U13B-IO_L08N_1-Pad98)") (class "Default")
      (node (ref "U13") (pin "98") (pinfunction "IO_L08N_1_98") (pintype "bidirectional+no_connect"))
    )
    (net (code "171") (name "unconnected-(U13B-IO_L08P_1-Pad96)") (class "Default")
      (node (ref "U13") (pin "96") (pinfunction "IO_L08P_1_96") (pintype "bidirectional+no_connect"))
    )
    (net (code "172") (name "unconnected-(U13B-IO_L09N_1-Pad101)") (class "Default")
      (node (ref "U13") (pin "101") (pinfunction "IO_L09N_1_101") (pintype "bidirectional+no_connect"))
    )
    (net (code "173") (name "unconnected-(U13B-IO_L09P_1-Pad99)") (class "Default")
      (node (ref "U13") (pin "99") (pinfunction "IO_L09P_1_99") (pintype "bidirectional+no_connect"))
    )
    (net (code "174") (name "unconnected-(U13B-IO_L10N_1-Pad104)") (class "Default")
      (node (ref "U13") (pin "104") (pinfunction "IO_L10N_1_104") (pintype "bidirectional+no_connect"))
    )
    (net (code "175") (name "unconnected-(U13B-IO_L10P_1-Pad102)") (class "Default")
      (node (ref "U13") (pin "102") (pinfunction "IO_L10P_1_102") (pintype "bidirectional"))
    )
    (net (code "176") (name "unconnected-(U13B-IO_L11N_1-Pad105)") (class "Default")
      (node (ref "U13") (pin "105") (pinfunction "IO_L11N_1_105") (pintype "bidirectional"))
    )
    (net (code "177") (name "unconnected-(U13B-IO_L11P_1-Pad103)") (class "Default")
      (node (ref "U13") (pin "103") (pinfunction "IO_L11P_1_103") (pintype "bidirectional"))
    )
    (net (code "178") (name "unconnected-(U13C-IO_L02P_2{slash}M2-Pad39)") (class "Default")
      (node (ref "U13") (pin "39") (pinfunction "IO_L02P_2/M2_39") (pintype "bidirectional"))
    )
    (net (code "179") (name "unconnected-(U13C-IO_L08N_2{slash}GCLK15-Pad55)") (class "Default")
      (node (ref "U13") (pin "55") (pinfunction "IO_L08N_2/GCLK15_55") (pintype "bidirectional+no_connect"))
    )
    (net (code "180") (name "unconnected-(U13C-IO_L11P_2{slash}AWAKE-Pad63)") (class "Default")
      (node (ref "U13") (pin "63") (pinfunction "IO_L11P_2/AWAKE_63") (pintype "bidirectional"))
    )
    (net (code "181") (name "unconnected-(U13E-IP_0-Pad140)") (class "Default")
      (node (ref "U13") (pin "140") (pinfunction "IP_0_140") (pintype "input+no_connect"))
    )
    (net (code "182") (name "unconnected-(U13E-IP_0{slash}VREF_0-Pad123)") (class "Default")
      (node (ref "U13") (pin "123") (pinfunction "IP_0/VREF_0_123") (pintype "input+no_connect"))
    )
    (net (code "183") (name "unconnected-(U13E-IP_1{slash}VREF_1-Pad80)") (class "Default")
      (node (ref "U13") (pin "80") (pinfunction "IP_1/VREF_1_80") (pintype "input+no_connect"))
    )
    (net (code "184") (name "unconnected-(U13E-IP_1{slash}VREF_1-Pad97)") (class "Default")
      (node (ref "U13") (pin "97") (pinfunction "IP_1/VREF_1_97") (pintype "input+no_connect"))
    )
    (net (code "185") (name "unconnected-(U13E-IP_2{slash}VREF_2-Pad53)") (class "Default")
      (node (ref "U13") (pin "53") (pinfunction "IP_2/VREF_2_53") (pintype "input+no_connect"))
    )
    (net (code "186") (name "unconnected-(U13E-IP_L13N_3{slash}VREF_3-Pad35)") (class "Default")
      (node (ref "U13") (pin "35") (pinfunction "IP_L13N_3/VREF_3_35") (pintype "input+no_connect"))
    )
    (net (code "187") (name "unconnected-(U13E-IP_L13P_3-Pad33)") (class "Default")
      (node (ref "U13") (pin "33") (pinfunction "IP_L13P_3_33") (pintype "input+no_connect"))
    )
    (net (code "188") (name "unconnected-(U13F-DONE-Pad73)") (class "Default")
      (node (ref "U13") (pin "73") (pinfunction "DONE_73") (pintype "bidirectional+no_connect"))
    )
    (net (code "189") (name "unconnected-(U13F-SUSPEND-Pad74)") (class "Default")
      (node (ref "U13") (pin "74") (pinfunction "SUSPEND_74") (pintype "input+no_connect"))
    )
    (net (code "190") (name "unconnected-(U15-NC-Pad4)") (class "Default")
      (node (ref "U15") (pin "4") (pinfunction "NC_4") (pintype "passive"))
    )
  )
)
